# DALI_Master.net
KiCad netlist of a schematic drawn in EAGLE
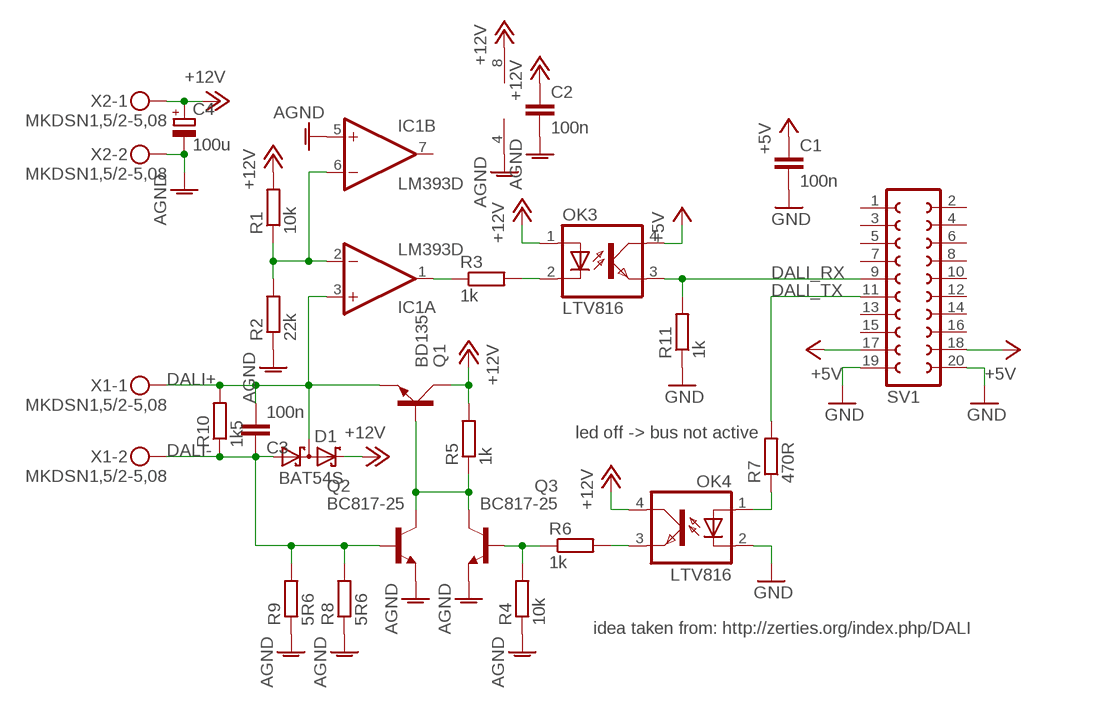
[diagram p0: schematic, sheet 1]

(export (version "E")
  (design (tool "Eeschema 10.0.6"))
  (components
    (comp (ref "C1")
      (value "100n")
      (footprint "eagle-import:C0805")
      (libsource (lib "eagle-import") (part "C-EUC0805"))
    )
    (comp (ref "C2")
      (value "100n")
      (footprint "eagle-import:C0805")
      (libsource (lib "eagle-import") (part "C-EUC0805"))
    )
    (comp (ref "C3")
      (value "100n")
      (footprint "eagle-import:C0805")
      (libsource (lib "eagle-import") (part "C-EUC0805"))
    )
    (comp (ref "C4")
      (value "100u")
      (footprint "eagle-import:E2,5-6")
      (libsource (lib "eagle-import") (part "CPOL-EUE2.5-6"))
    )
    (comp (ref "D1")
      (value "BAT54S")
      (footprint "eagle-import:SOT23")
      (libsource (lib "eagle-import") (part "BAT54S"))
    )
    (comp (ref "IC1")
      (value "LM393D")
      (footprint "eagle-import:SO08")
      (libsource (lib "eagle-import") (part "LM393D"))
    )
    (comp (ref "OK3")
      (value "LTV816")
      (footprint "eagle-import:DIL04")
      (libsource (lib "eagle-import") (part "LTV816"))
    )
    (comp (ref "OK4")
      (value "LTV816")
      (footprint "eagle-import:DIL04")
      (libsource (lib "eagle-import") (part "LTV816"))
    )
    (comp (ref "Q1")
      (value "BD135")
      (footprint "eagle-import:TO126AV")
      (libsource (lib "eagle-import") (part "BD139"))
    )
    (comp (ref "Q2")
      (value "BC817-25")
      (footprint "eagle-import:SOT23-BEC")
      (libsource (lib "eagle-import") (part "BC817SMD-25"))
    )
    (comp (ref "Q3")
      (value "BC817-25")
      (footprint "eagle-import:SOT23-BEC")
      (libsource (lib "eagle-import") (part "BC817SMD-25"))
    )
    (comp (ref "R1")
      (value "10k")
      (footprint "eagle-import:R0805")
      (libsource (lib "eagle-import") (part "R-EU_R0805"))
    )
    (comp (ref "R2")
      (value "22k")
      (footprint "eagle-import:R0805")
      (libsource (lib "eagle-import") (part "R-EU_R0805"))
    )
    (comp (ref "R3")
      (value "1k")
      (footprint "eagle-import:R0805")
      (libsource (lib "eagle-import") (part "R-EU_R0805"))
    )
    (comp (ref "R4")
      (value "10k")
      (footprint "eagle-import:R0805")
      (libsource (lib "eagle-import") (part "R-EU_R0805"))
    )
    (comp (ref "R5")
      (value "1k")
      (footprint "eagle-import:R0805")
      (libsource (lib "eagle-import") (part "R-EU_R0805"))
    )
    (comp (ref "R6")
      (value "1k")
      (footprint "eagle-import:R0805")
      (libsource (lib "eagle-import") (part "R-EU_R0805"))
    )
    (comp (ref "R7")
      (value "470R")
      (footprint "eagle-import:R0805")
      (libsource (lib "eagle-import") (part "R-EU_R0805"))
    )
    (comp (ref "R8")
      (value "5R6")
      (footprint "eagle-import:R1206")
      (libsource (lib "eagle-import") (part "R-EU_R1206"))
    )
    (comp (ref "R9")
      (value "5R6")
      (footprint "eagle-import:R1206")
      (libsource (lib "eagle-import") (part "R-EU_R1206"))
    )
    (comp (ref "R10")
      (value "1k5")
      (footprint "eagle-import:R0805")
      (libsource (lib "eagle-import") (part "R-EU_R0805"))
    )
    (comp (ref "R11")
      (value "1k")
      (footprint "eagle-import:R0805")
      (libsource (lib "eagle-import") (part "R-EU_R0805"))
    )
    (comp (ref "SV1")
      (value "FE10-2")
      (footprint "eagle-import:FE10-2")
      (libsource (lib "eagle-import") (part "FE10-2"))
    )
    (comp (ref "X1")
      (value "MKDSN1,5/2-5,08")
      (footprint "eagle-import:MKDSN1,5_2-5,08")
      (fields (field (name "MPN") "MKDSN 1,5/2-5.08"))
      (libsource (lib "eagle-import") (part "MKDSN1,5/2-5,08"))
    )
    (comp (ref "X2")
      (value "MKDSN1,5/2-5,08")
      (footprint "eagle-import:MKDSN1,5_2-5,08")
      (fields (field (name "MPN") "MKDSN 1,5/2-5.08"))
      (libsource (lib "eagle-import") (part "MKDSN1,5/2-5,08"))
    )
  )
  (nets
    (net (code "1") (name "+5V") (class "Default")
      (node (ref "C1") (pin "1") (pinfunction "1_1") (pintype "passive"))
      (node (ref "OK3") (pin "4") (pinfunction "COL_4") (pintype "passive"))
      (node (ref "SV1") (pin "17") (pinfunction "17_17") (pintype "passive"))
      (node (ref "SV1") (pin "18") (pinfunction "18_18") (pintype "passive"))
    )
    (net (code "2") (name "+12V") (class "Default")
      (node (ref "C2") (pin "1") (pinfunction "1_1") (pintype "passive"))
      (node (ref "C4") (pin "+") (pinfunction "+_+") (pintype "passive"))
      (node (ref "D1") (pin "2") (pinfunction "C2_2") (pintype "passive"))
      (node (ref "IC1") (pin "8") (pinfunction "V+_8") (pintype "power_in"))
      (node (ref "OK3") (pin "1") (pinfunction "A_1") (pintype "passive"))
      (node (ref "OK4") (pin "4") (pinfunction "COL_4") (pintype "passive"))
      (node (ref "Q1") (pin "C") (pinfunction "C_C") (pintype "passive"))
      (node (ref "R1") (pin "2") (pinfunction "2_2") (pintype "passive"))
      (node (ref "R5") (pin "2") (pinfunction "2_2") (pintype "passive"))
      (node (ref "X2") (pin "1") (pinfunction "KL_1") (pintype "passive"))
    )
    (net (code "3") (name "/DALI+") (class "Default")
      (node (ref "C3") (pin "2") (pinfunction "2_2") (pintype "passive"))
      (node (ref "D1") (pin "3") (pinfunction "C1A2_3") (pintype "passive"))
      (node (ref "IC1") (pin "3") (pinfunction "+IN_3") (pintype "input"))
      (node (ref "Q1") (pin "E") (pinfunction "E_E") (pintype "passive"))
      (node (ref "R10") (pin "2") (pinfunction "2_2") (pintype "passive"))
      (node (ref "X1") (pin "1") (pinfunction "KL_1") (pintype "passive"))
    )
    (net (code "4") (name "/DALI-") (class "Default")
      (node (ref "C3") (pin "1") (pinfunction "1_1") (pintype "passive"))
      (node (ref "D1") (pin "1") (pinfunction "A1_1") (pintype "passive"))
      (node (ref "Q2") (pin "B") (pinfunction "B_B") (pintype "passive"))
      (node (ref "R10") (pin "1") (pinfunction "1_1") (pintype "passive"))
      (node (ref "R8") (pin "2") (pinfunction "2_2") (pintype "passive"))
      (node (ref "R9") (pin "2") (pinfunction "2_2") (pintype "passive"))
      (node (ref "X1") (pin "2") (pinfunction "KL_2") (pintype "passive"))
    )
    (net (code "5") (name "/DALI_RX") (class "Default")
      (node (ref "OK3") (pin "3") (pinfunction "EMIT_3") (pintype "passive"))
      (node (ref "R11") (pin "2") (pinfunction "2_2") (pintype "passive"))
      (node (ref "SV1") (pin "9") (pinfunction "9_9") (pintype "passive"))
    )
    (net (code "6") (name "/DALI_TX") (class "Default")
      (node (ref "R7") (pin "2") (pinfunction "2_2") (pintype "passive"))
      (node (ref "SV1") (pin "11") (pinfunction "11_11") (pintype "passive"))
    )
    (net (code "7") (name "AGND") (class "Default")
      (node (ref "C2") (pin "2") (pinfunction "2_2") (pintype "passive"))
      (node (ref "C4") (pin "-") (pinfunction "-_-") (pintype "passive"))
      (node (ref "IC1") (pin "4") (pinfunction "V-_4") (pintype "power_in"))
      (node (ref "IC1") (pin "5") (pinfunction "+IN_5") (pintype "input"))
      (node (ref "Q2") (pin "E") (pinfunction "E_E") (pintype "passive"))
      (node (ref "Q3") (pin "E") (pinfunction "E_E") (pintype "passive"))
      (node (ref "R2") (pin "1") (pinfunction "1_1") (pintype "passive"))
      (node (ref "R4") (pin "1") (pinfunction "1_1") (pintype "passive"))
      (node (ref "R8") (pin "1") (pinfunction "1_1") (pintype "passive"))
      (node (ref "R9") (pin "1") (pinfunction "1_1") (pintype "passive"))
      (node (ref "X2") (pin "2") (pinfunction "KL_2") (pintype "passive"))
    )
    (net (code "8") (name "GND") (class "Default")
      (node (ref "C1") (pin "2") (pinfunction "2_2") (pintype "passive"))
      (node (ref "OK4") (pin "2") (pinfunction "C_2") (pintype "passive"))
      (node (ref "R11") (pin "1") (pinfunction "1_1") (pintype "passive"))
      (node (ref "SV1") (pin "19") (pinfunction "19_19") (pintype "passive"))
      (node (ref "SV1") (pin "20") (pinfunction "20_20") (pintype "passive"))
    )
    (net (code "9") (name "Net-(IC1A--IN)") (class "Default")
      (node (ref "IC1") (pin "2") (pinfunction "-IN_2") (pintype "input"))
      (node (ref "IC1") (pin "6") (pinfunction "-IN_6") (pintype "input"))
      (node (ref "R1") (pin "1") (pinfunction "1_1") (pintype "passive"))
      (node (ref "R2") (pin "2") (pinfunction "2_2") (pintype "passive"))
    )
    (net (code "10") (name "Net-(IC1A-OUT)") (class "Default")
      (node (ref "IC1") (pin "1") (pinfunction "OUT_1") (pintype "output"))
      (node (ref "R3") (pin "1") (pinfunction "1_1") (pintype "passive"))
    )
    (net (code "11") (name "Net-(OK3-C)") (class "Default")
      (node (ref "OK3") (pin "2") (pinfunction "C_2") (pintype "passive"))
      (node (ref "R3") (pin "2") (pinfunction "2_2") (pintype "passive"))
    )
    (net (code "12") (name "Net-(OK4-A)") (class "Default")
      (node (ref "OK4") (pin "1") (pinfunction "A_1") (pintype "passive"))
      (node (ref "R7") (pin "1") (pinfunction "1_1") (pintype "passive"))
    )
    (net (code "13") (name "Net-(OK4-EMIT)") (class "Default")
      (node (ref "OK4") (pin "3") (pinfunction "EMIT_3") (pintype "passive"))
      (node (ref "R6") (pin "2") (pinfunction "2_2") (pintype "passive"))
    )
    (net (code "14") (name "Net-(Q1-PadB)") (class "Default")
      (node (ref "Q1") (pin "B") (pinfunction "B_B") (pintype "passive"))
      (node (ref "Q2") (pin "C") (pinfunction "C_C") (pintype "passive"))
      (node (ref "Q3") (pin "C") (pinfunction "C_C") (pintype "passive"))
      (node (ref "R5") (pin "1") (pinfunction "1_1") (pintype "passive"))
    )
    (net (code "15") (name "Net-(Q3-PadB)") (class "Default")
      (node (ref "Q3") (pin "B") (pinfunction "B_B") (pintype "passive"))
      (node (ref "R4") (pin "2") (pinfunction "2_2") (pintype "passive"))
      (node (ref "R6") (pin "1") (pinfunction "1_1") (pintype "passive"))
    )
    (net (code "16") (name "unconnected-(IC1B-OUT-Pad7)") (class "Default")
      (node (ref "IC1") (pin "7") (pinfunction "OUT_7") (pintype "output"))
    )
    (net (code "17") (name "unconnected-(SV1-Pad1)") (class "Default")
      (node (ref "SV1") (pin "1") (pinfunction "1_1") (pintype "passive"))
    )
    (net (code "18") (name "unconnected-(SV1-Pad2)") (class "Default")
      (node (ref "SV1") (pin "2") (pinfunction "2_2") (pintype "passive"))
    )
    (net (code "19") (name "unconnected-(SV1-Pad3)") (class "Default")
      (node (ref "SV1") (pin "3") (pinfunction "3_3") (pintype "passive"))
    )
    (net (code "20") (name "unconnected-(SV1-Pad4)") (class "Default")
      (node (ref "SV1") (pin "4") (pinfunction "4_4") (pintype "passive"))
    )
    (net (code "21") (name "unconnected-(SV1-Pad5)") (class "Default")
      (node (ref "SV1") (pin "5") (pinfunction "5_5") (pintype "passive"))
    )
    (net (code "22") (name "unconnected-(SV1-Pad6)") (class "Default")
      (node (ref "SV1") (pin "6") (pinfunction "6_6") (pintype "passive"))
    )
    (net (code "23") (name "unconnected-(SV1-Pad7)") (class "Default")
      (node (ref "SV1") (pin "7") (pinfunction "7_7") (pintype "passive"))
    )
    (net (code "24") (name "unconnected-(SV1-Pad8)") (class "Default")
      (node (ref "SV1") (pin "8") (pinfunction "8_8") (pintype "passive"))
    )
    (net (code "25") (name "unconnected-(SV1-Pad10)") (class "Default")
      (node (ref "SV1") (pin "10") (pinfunction "10_10") (pintype "passive"))
    )
    (net (code "26") (name "unconnected-(SV1-Pad12)") (class "Default")
      (node (ref "SV1") (pin "12") (pinfunction "12_12") (pintype "passive"))
    )
    (net (code "27") (name "unconnected-(SV1-Pad13)") (class "Default")
      (node (ref "SV1") (pin "13") (pinfunction "13_13") (pintype "passive"))
    )
    (net (code "28") (name "unconnected-(SV1-Pad14)") (class "Default")
      (node (ref "SV1") (pin "14") (pinfunction "14_14") (pintype "passive"))
    )
    (net (code "29") (name "unconnected-(SV1-Pad15)") (class "Default")
      (node (ref "SV1") (pin "15") (pinfunction "15_15") (pintype "passive"))
    )
    (net (code "30") (name "unconnected-(SV1-Pad16)") (class "Default")
      (node (ref "SV1") (pin "16") (pinfunction "16_16") (pintype "passive"))
    )
  )
)
